# design.net
KiCad netlist of a schematic drawn in EasyEDA Pro
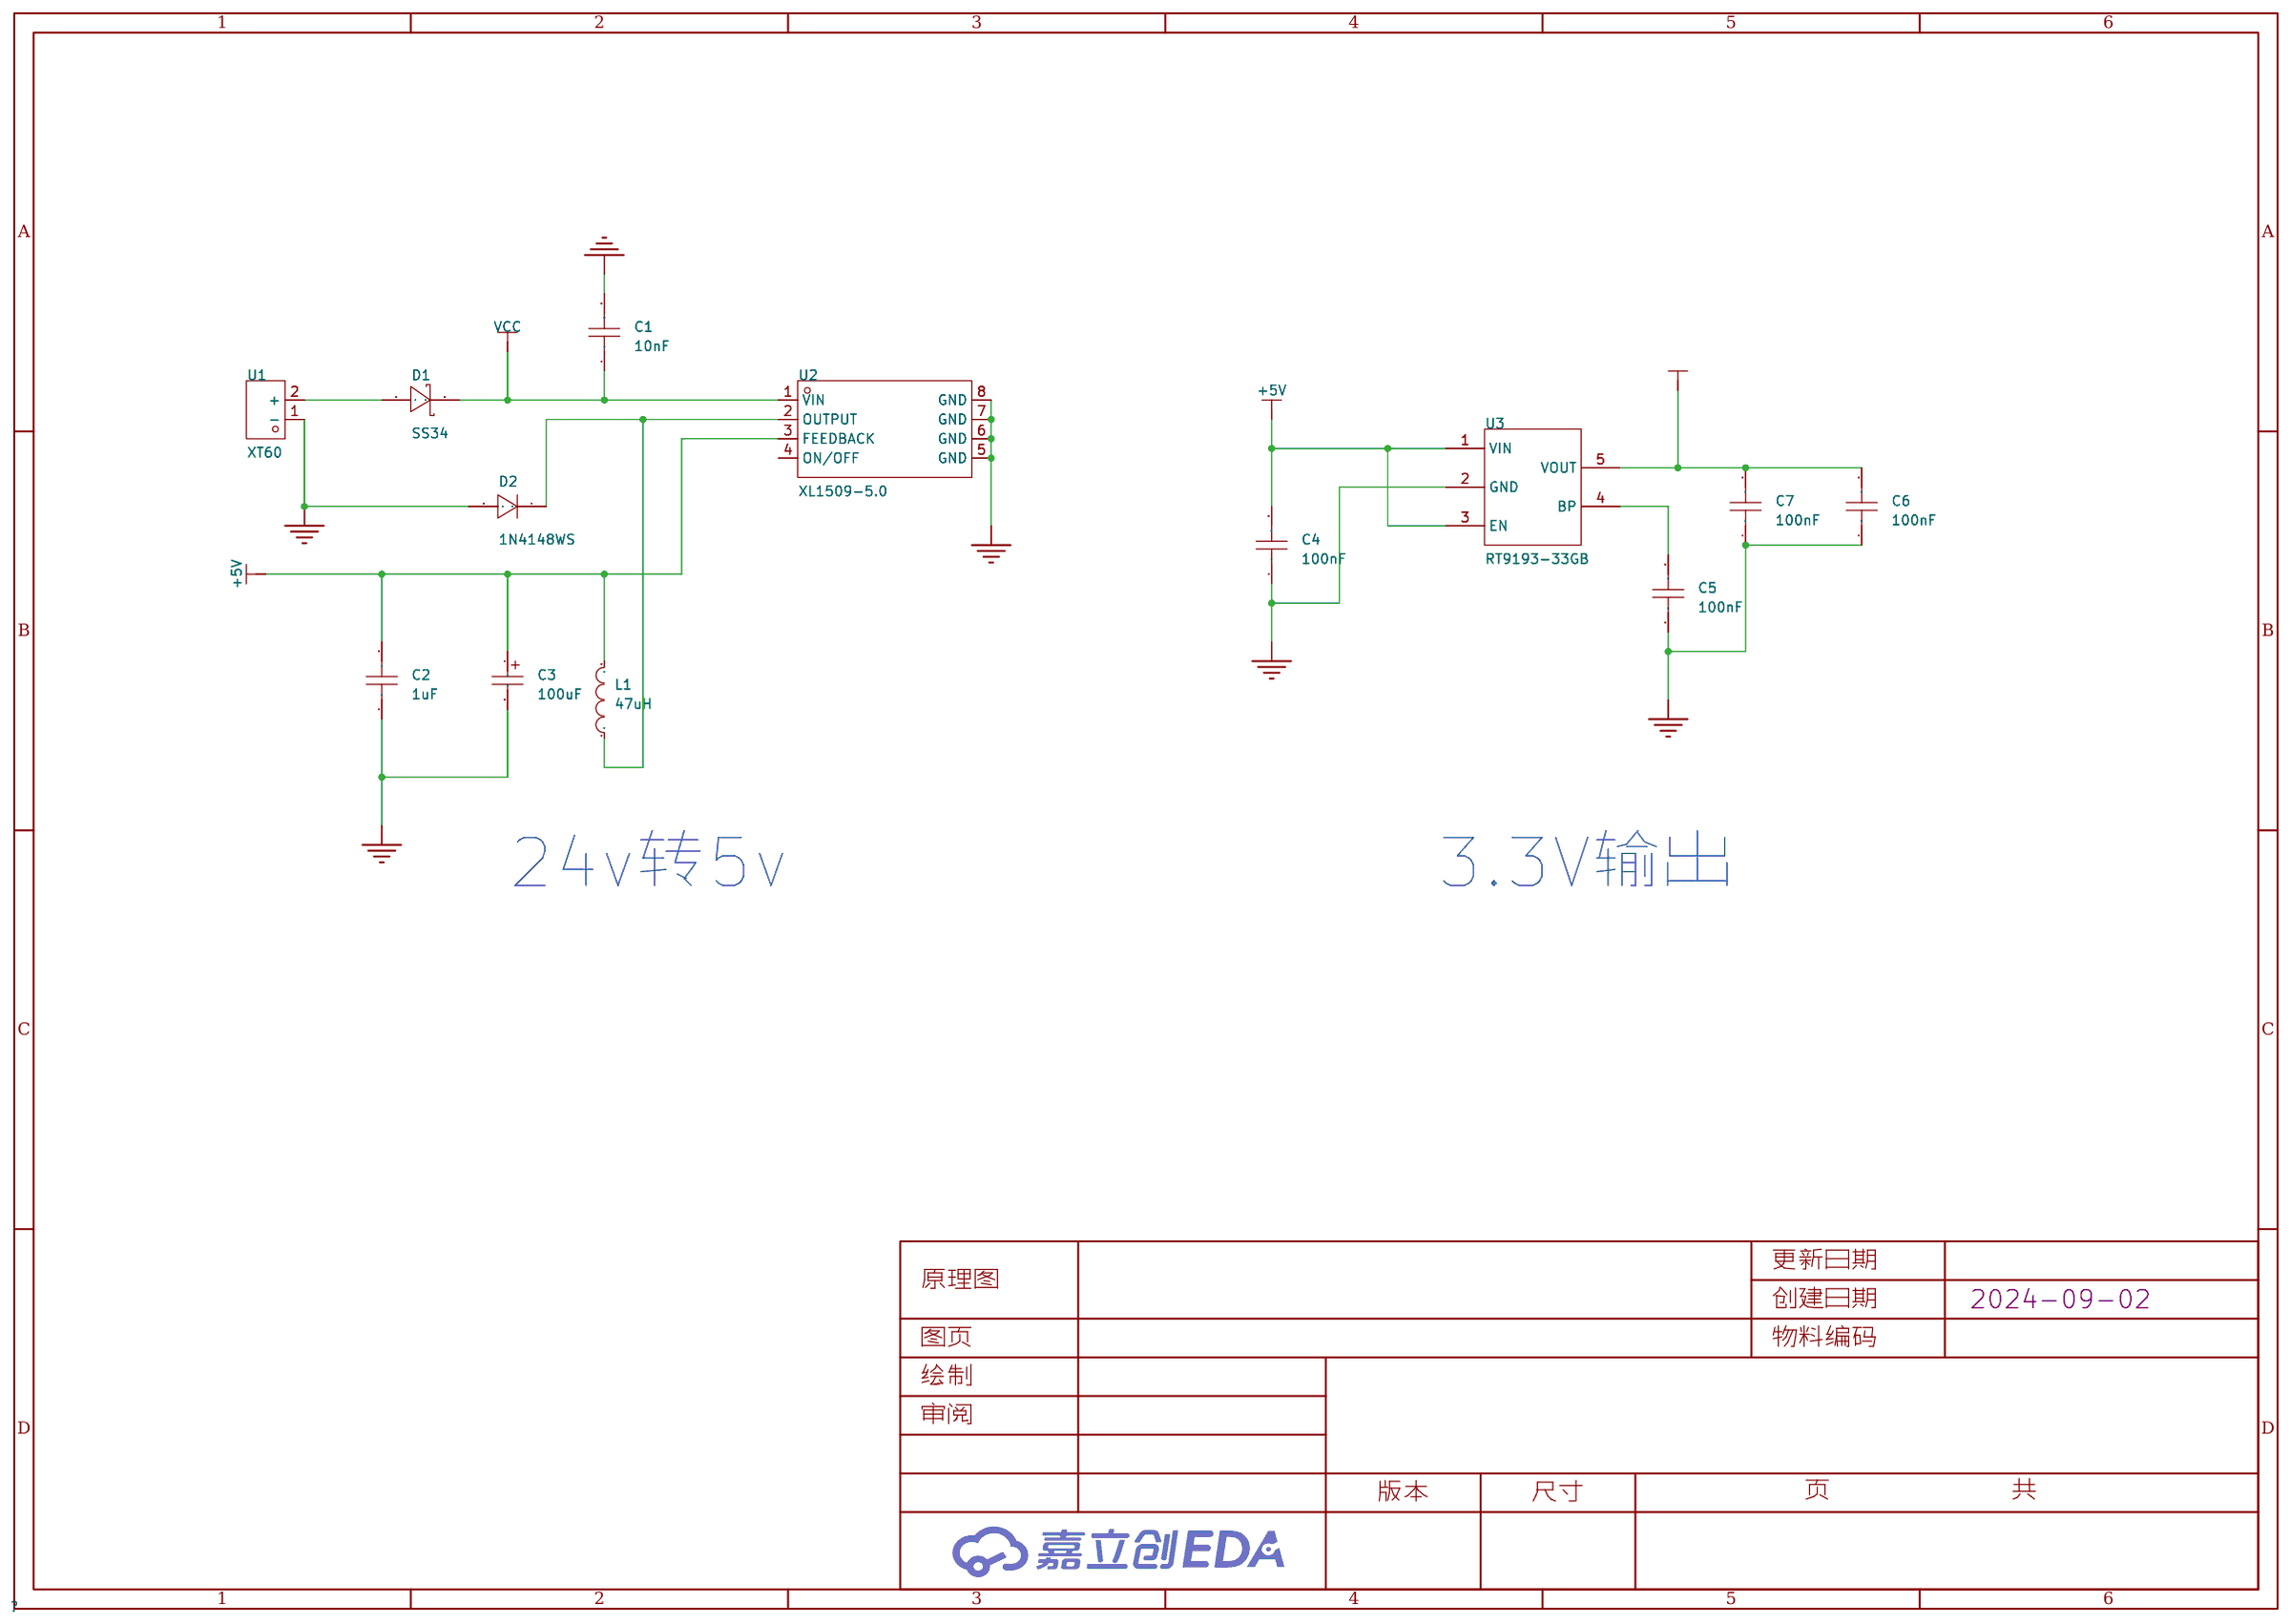
[diagram p0: schematic sheet]

(export (version "E")
  (design (tool "Eeschema 10.0.6"))
  (components
    (comp (ref "C1")
      (value "10nF")
      (footprint "easyedapro:C0603")
      (libsource (lib "easyedapro") (part "CapAcitance"))
    )
    (comp (ref "C2")
      (value "1uF")
      (footprint "easyedapro:C0603")
      (libsource (lib "easyedapro") (part "CapAcitance"))
    )
    (comp (ref "C3")
      (value "100uF")
      (footprint "easyedapro:C_Ele_SMD_3x5.4mm")
      (libsource (lib "easyedapro") (part "CAP"))
    )
    (comp (ref "C4")
      (value "100nF")
      (footprint "easyedapro:C0603")
      (libsource (lib "easyedapro") (part "CapAcitance"))
    )
    (comp (ref "C5")
      (value "100nF")
      (footprint "easyedapro:C0603")
      (libsource (lib "easyedapro") (part "CapAcitance"))
    )
    (comp (ref "C6")
      (value "100nF")
      (footprint "easyedapro:C0603")
      (libsource (lib "easyedapro") (part "CapAcitance"))
    )
    (comp (ref "C7")
      (value "100nF")
      (footprint "easyedapro:C0603")
      (libsource (lib "easyedapro") (part "CapAcitance"))
    )
    (comp (ref "D1")
      (value "SS34")
      (footprint "easyedapro:SMA_L4.3-W2.6-LS5.2-RD")
      (description "二极管配置:独立式;正向压降(Vf):550mV@3A;直流反向耐压(Vr):40V;整流电流:3A;")
      (fields (field (name "Manufacturer") "MDD(辰达半导体)"))
      (libsource (lib "easyedapro") (part "SS34_C8678"))
    )
    (comp (ref "D2")
      (value "1N4148WS")
      (footprint "easyedapro:SOD-323_L1.8-W1.3-LS2.5-RD")
      (description "二极管配置:独立式;正向压降(Vf):1.25V@150mA;直流反向耐压(Vr):100V;平均整流电流(Io):150mA;功率:200mW;反向恢复时间(trr):4ns;")
      (fields (field (name "Manufacturer") "CJ(江苏长电/长晶)"))
      (libsource (lib "easyedapro") (part "1N4148WS T4"))
    )
    (comp (ref "L1")
      (value "47uH")
      (footprint "easyedapro:L0603")
      (libsource (lib "easyedapro") (part "SDFL1608S100KTF"))
    )
    (comp (ref "U1")
      (value "XT60")
      (footprint "easyedapro:CONN-TH_XT60")
      (description "类别:-;类型1:-;")
      (fields (field (name "Manufacturer") "AMASS(艾迈斯)"))
      (libsource (lib "easyedapro") (part "XT60"))
    )
    (comp (ref "U2")
      (value "XL1509-5.0")
      (footprint "easyedapro:SOIC-8_L4.9-W3.9-P1.27-LS6.0-TR")
      (fields (field (name "Manufacturer") "UMW(友台半导体)"))
      (libsource (lib "easyedapro") (part "XL1509-5.0_C2902368"))
    )
    (comp (ref "U3")
      (value "RT9193-33GB")
      (footprint "easyedapro:SOT-23-5_L3.0-W1.7-P0.95-LS2.8-BL")
      (description "输出类型:固定;最大输入电压:5.5V;输出电压:3.3V;最大输出电流:300mA;电源纹波抑制比(PSRR):70dB;输出极性:正极;")
      (fields (field (name "Manufacturer") "RICHTEK(立锜)"))
      (libsource (lib "easyedapro") (part "RT9193-33GB"))
    )
  )
  (nets
    (net (code "1") (name "+5V") (class "Default")
      (node (ref "C2") (pin "2") (pinfunction "2_2") (pintype "input"))
      (node (ref "C3") (pin "1") (pinfunction "1_1") (pintype "input"))
      (node (ref "C4") (pin "2") (pinfunction "2_2") (pintype "input"))
      (node (ref "L1") (pin "2") (pinfunction "2_2") (pintype "unspecified"))
      (node (ref "U2") (pin "3") (pinfunction "FEEDBACK_3") (pintype "unspecified"))
      (node (ref "U3") (pin "1") (pinfunction "VIN_1") (pintype "unspecified"))
      (node (ref "U3") (pin "3") (pinfunction "EN_3") (pintype "unspecified"))
    )
    (net (code "2") (name "3.3V") (class "Default")
      (node (ref "C6") (pin "2") (pinfunction "2_2") (pintype "input"))
      (node (ref "C7") (pin "2") (pinfunction "2_2") (pintype "input"))
      (node (ref "U3") (pin "5") (pinfunction "VOUT_5") (pintype "unspecified"))
    )
    (net (code "3") (name "GND") (class "Default")
      (node (ref "C1") (pin "2") (pinfunction "2_2") (pintype "input"))
      (node (ref "C2") (pin "1") (pinfunction "1_1") (pintype "input"))
      (node (ref "C3") (pin "2") (pinfunction "2_2") (pintype "input"))
      (node (ref "C4") (pin "1") (pinfunction "1_1") (pintype "input"))
      (node (ref "C5") (pin "1") (pinfunction "1_1") (pintype "input"))
      (node (ref "C6") (pin "1") (pinfunction "1_1") (pintype "input"))
      (node (ref "C7") (pin "1") (pinfunction "1_1") (pintype "input"))
      (node (ref "D2") (pin "2") (pinfunction "A_2") (pintype "unspecified"))
      (node (ref "U1") (pin "1") (pinfunction "-_1") (pintype "input"))
      (node (ref "U2") (pin "5") (pinfunction "GND_5") (pintype "unspecified"))
      (node (ref "U2") (pin "6") (pinfunction "GND_6") (pintype "unspecified"))
      (node (ref "U2") (pin "7") (pinfunction "GND_7") (pintype "unspecified"))
      (node (ref "U2") (pin "8") (pinfunction "GND_8") (pintype "unspecified"))
      (node (ref "U3") (pin "2") (pinfunction "GND_2") (pintype "unspecified"))
    )
    (net (code "4") (name "Net-(D1-A)") (class "Default")
      (node (ref "D1") (pin "2") (pinfunction "A_2") (pintype "unspecified"))
      (node (ref "U1") (pin "2") (pinfunction "+_2") (pintype "input"))
    )
    (net (code "5") (name "Net-(D2-K)") (class "Default")
      (node (ref "D2") (pin "1") (pinfunction "K_1") (pintype "unspecified"))
      (node (ref "L1") (pin "1") (pinfunction "1_1") (pintype "unspecified"))
      (node (ref "U2") (pin "2") (pinfunction "OUTPUT_2") (pintype "unspecified"))
    )
    (net (code "6") (name "Net-(U3-BP)") (class "Default")
      (node (ref "C5") (pin "2") (pinfunction "2_2") (pintype "input"))
      (node (ref "U3") (pin "4") (pinfunction "BP_4") (pintype "unspecified"))
    )
    (net (code "7") (name "VCC") (class "Default")
      (node (ref "C1") (pin "1") (pinfunction "1_1") (pintype "input"))
      (node (ref "D1") (pin "1") (pinfunction "K_1") (pintype "unspecified"))
      (node (ref "U2") (pin "1") (pinfunction "VIN_1") (pintype "unspecified"))
    )
    (net (code "8") (name "unconnected-(U2-ON{slash}OFF-Pad4)") (class "Default")
      (node (ref "U2") (pin "4") (pinfunction "ON/OFF_4") (pintype "unspecified"))
    )
  )
)
